# 4_TPS63060_--.net
KiCad netlist of a schematic drawn in Altium Designer
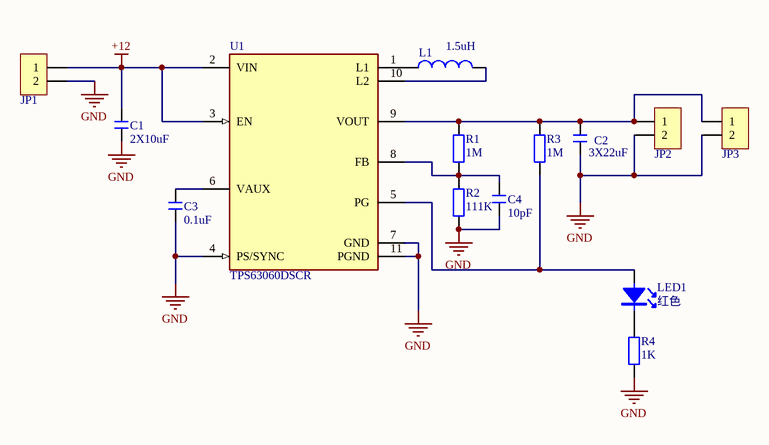
[diagram p0: 4_TPS63060降压--升压转换器.SchDoc]

(export (version "E")
  (design (tool "Eeschema 10.0.6"))
  (components
    (comp (ref "C1")
      (value "2X10uF")
      (footprint "C 0805_L")
      (description "贴片电容")
      (libsource (lib "01 - 电容-电阻-电感") (part "C"))
    )
    (comp (ref "C2")
      (value "3X22uF")
      (footprint "C 0805_L")
      (description "贴片电容")
      (libsource (lib "01 - 电容-电阻-电感") (part "C"))
    )
    (comp (ref "C3")
      (value "0.1uF")
      (footprint "C 0805_L")
      (description "贴片电容")
      (libsource (lib "01 - 电容-电阻-电感") (part "C"))
    )
    (comp (ref "C4")
      (value "10pF")
      (footprint "C 0805_L")
      (description "贴片电容")
      (libsource (lib "01 - 电容-电阻-电感") (part "C"))
    )
    (comp (ref "JP1")
      (value "HDR-1X2")
      (footprint "KF2EDGK5.08-WI-2P")
      (description "2P接插件")
      (libsource (lib "22 - 接插件-脚距5.08mm (200mil) ") (part "Header 2"))
    )
    (comp (ref "JP2")
      (value "HDR-1X2")
      (footprint "HDR2.54-WI-2P")
      (description "2P接插件")
      (libsource (lib "17 - 接插件-脚距2.54mm (100mil) ") (part "Header 2"))
    )
    (comp (ref "JP3")
      (value "HDR-1X2")
      (footprint "HDR2.54-WI-2P")
      (description "2P接插件")
      (libsource (lib "17 - 接插件-脚距2.54mm (100mil) ") (part "Header 2"))
    )
    (comp (ref "L1")
      (value "1.5uH")
      (footprint "L 0805")
      (description "小功率贴片电感")
      (libsource (lib "01 - 电容-电阻-电感") (part "L"))
    )
    (comp (ref "LED1")
      (value "红色")
      (footprint "LED 0805G")
      (description "贴片LED")
      (libsource (lib "02 - 二极管(LED)-三极管-整流桥") (part "LED-SMD"))
    )
    (comp (ref "R1")
      (value "1M")
      (footprint "R 0805_L")
      (description "贴片电阻")
      (libsource (lib "01 - 电容-电阻-电感") (part "R"))
    )
    (comp (ref "R2")
      (value "111K")
      (footprint "R 0805_L")
      (description "贴片电阻")
      (libsource (lib "01 - 电容-电阻-电感") (part "R"))
    )
    (comp (ref "R3")
      (value "1M")
      (footprint "R 0805_L")
      (description "贴片电阻")
      (libsource (lib "01 - 电容-电阻-电感") (part "R"))
    )
    (comp (ref "R4")
      (value "1K")
      (footprint "R 0805_L")
      (description "贴片电阻")
      (libsource (lib "01 - 电容-电阻-电感") (part "R"))
    )
    (comp (ref "U1")
      (value "TPS63060DSCR")
      (footprint "FP-DSC0010G-MFG")
      (description "IC REG BCK BST ADJ 2A 10WSON")
      (fields
        (field (name "OCTOPART") "https://octopart.com/tps63060dscr-texas+instruments-21396306")
        (field (name "MANUFACTURER") "Texas Instruments")
      )
      (libsource (lib "Altium Content Vault") (part "685ee7cb3382eb91975488bbdb76012"))
    )
  )
  (nets
    (net (code "1") (name "+12") (class "Default")
      (node (ref "C1") (pin "2") (pinfunction "2_2") (pintype "passive"))
      (node (ref "JP1") (pin "1") (pinfunction "1_1") (pintype "passive"))
      (node (ref "U1") (pin "2") (pinfunction "VIN_2") (pintype "power_in"))
      (node (ref "U1") (pin "3") (pinfunction "EN_3") (pintype "input"))
    )
    (net (code "2") (name "GND") (class "Default")
      (node (ref "C1") (pin "1") (pinfunction "1_1") (pintype "passive"))
      (node (ref "C2") (pin "1") (pinfunction "1_1") (pintype "passive"))
      (node (ref "C3") (pin "1") (pinfunction "1_1") (pintype "passive"))
      (node (ref "C4") (pin "1") (pinfunction "1_1") (pintype "passive"))
      (node (ref "JP1") (pin "2") (pinfunction "2_2") (pintype "passive"))
      (node (ref "JP2") (pin "2") (pinfunction "2_2") (pintype "passive"))
      (node (ref "JP3") (pin "2") (pinfunction "2_2") (pintype "passive"))
      (node (ref "R2") (pin "1") (pinfunction "1_1") (pintype "passive"))
      (node (ref "R4") (pin "1") (pinfunction "1_1") (pintype "passive"))
      (node (ref "U1") (pin "11") (pinfunction "PGND_11") (pintype "power_in"))
      (node (ref "U1") (pin "4") (pinfunction "PS/SYNC_4") (pintype "input"))
      (node (ref "U1") (pin "7") (pinfunction "GND_7") (pintype "power_in"))
    )
    (net (code "3") (name "Net-(LED1-A)") (class "Default")
      (node (ref "LED1") (pin "1") (pinfunction "A_1") (pintype "passive"))
      (node (ref "R3") (pin "1") (pinfunction "1_1") (pintype "passive"))
      (node (ref "U1") (pin "5") (pinfunction "PG_5") (pintype "open_collector"))
    )
    (net (code "4") (name "Net-(LED1-K)") (class "Default")
      (node (ref "LED1") (pin "2") (pinfunction "K_2") (pintype "passive"))
      (node (ref "R4") (pin "2") (pinfunction "2_2") (pintype "passive"))
    )
    (net (code "5") (name "Net-(U1-FB)") (class "Default")
      (node (ref "C4") (pin "2") (pinfunction "2_2") (pintype "passive"))
      (node (ref "R1") (pin "1") (pinfunction "1_1") (pintype "passive"))
      (node (ref "R2") (pin "2") (pinfunction "2_2") (pintype "passive"))
      (node (ref "U1") (pin "8") (pinfunction "FB_8") (pintype "passive"))
    )
    (net (code "6") (name "Net-(U1-L1)") (class "Default")
      (node (ref "L1") (pin "1") (pinfunction "1_1") (pintype "passive"))
      (node (ref "U1") (pin "1") (pinfunction "L1_1") (pintype "passive"))
    )
    (net (code "7") (name "Net-(U1-L2)") (class "Default")
      (node (ref "L1") (pin "2") (pinfunction "2_2") (pintype "passive"))
      (node (ref "U1") (pin "10") (pinfunction "L2_10") (pintype "passive"))
    )
    (net (code "8") (name "Net-(U1-VAUX)") (class "Default")
      (node (ref "C3") (pin "2") (pinfunction "2_2") (pintype "passive"))
      (node (ref "U1") (pin "6") (pinfunction "VAUX_6") (pintype "passive"))
    )
    (net (code "9") (name "Net-(U1-VOUT)") (class "Default")
      (node (ref "C2") (pin "2") (pinfunction "2_2") (pintype "passive"))
      (node (ref "JP2") (pin "1") (pinfunction "1_1") (pintype "passive"))
      (node (ref "JP3") (pin "1") (pinfunction "1_1") (pintype "passive"))
      (node (ref "R1") (pin "2") (pinfunction "2_2") (pintype "passive"))
      (node (ref "R3") (pin "2") (pinfunction "2_2") (pintype "passive"))
      (node (ref "U1") (pin "9") (pinfunction "VOUT_9") (pintype "power_in"))
    )
  )
)
